# 64.net
KiCad netlist of a schematic drawn in EasyEDA Pro
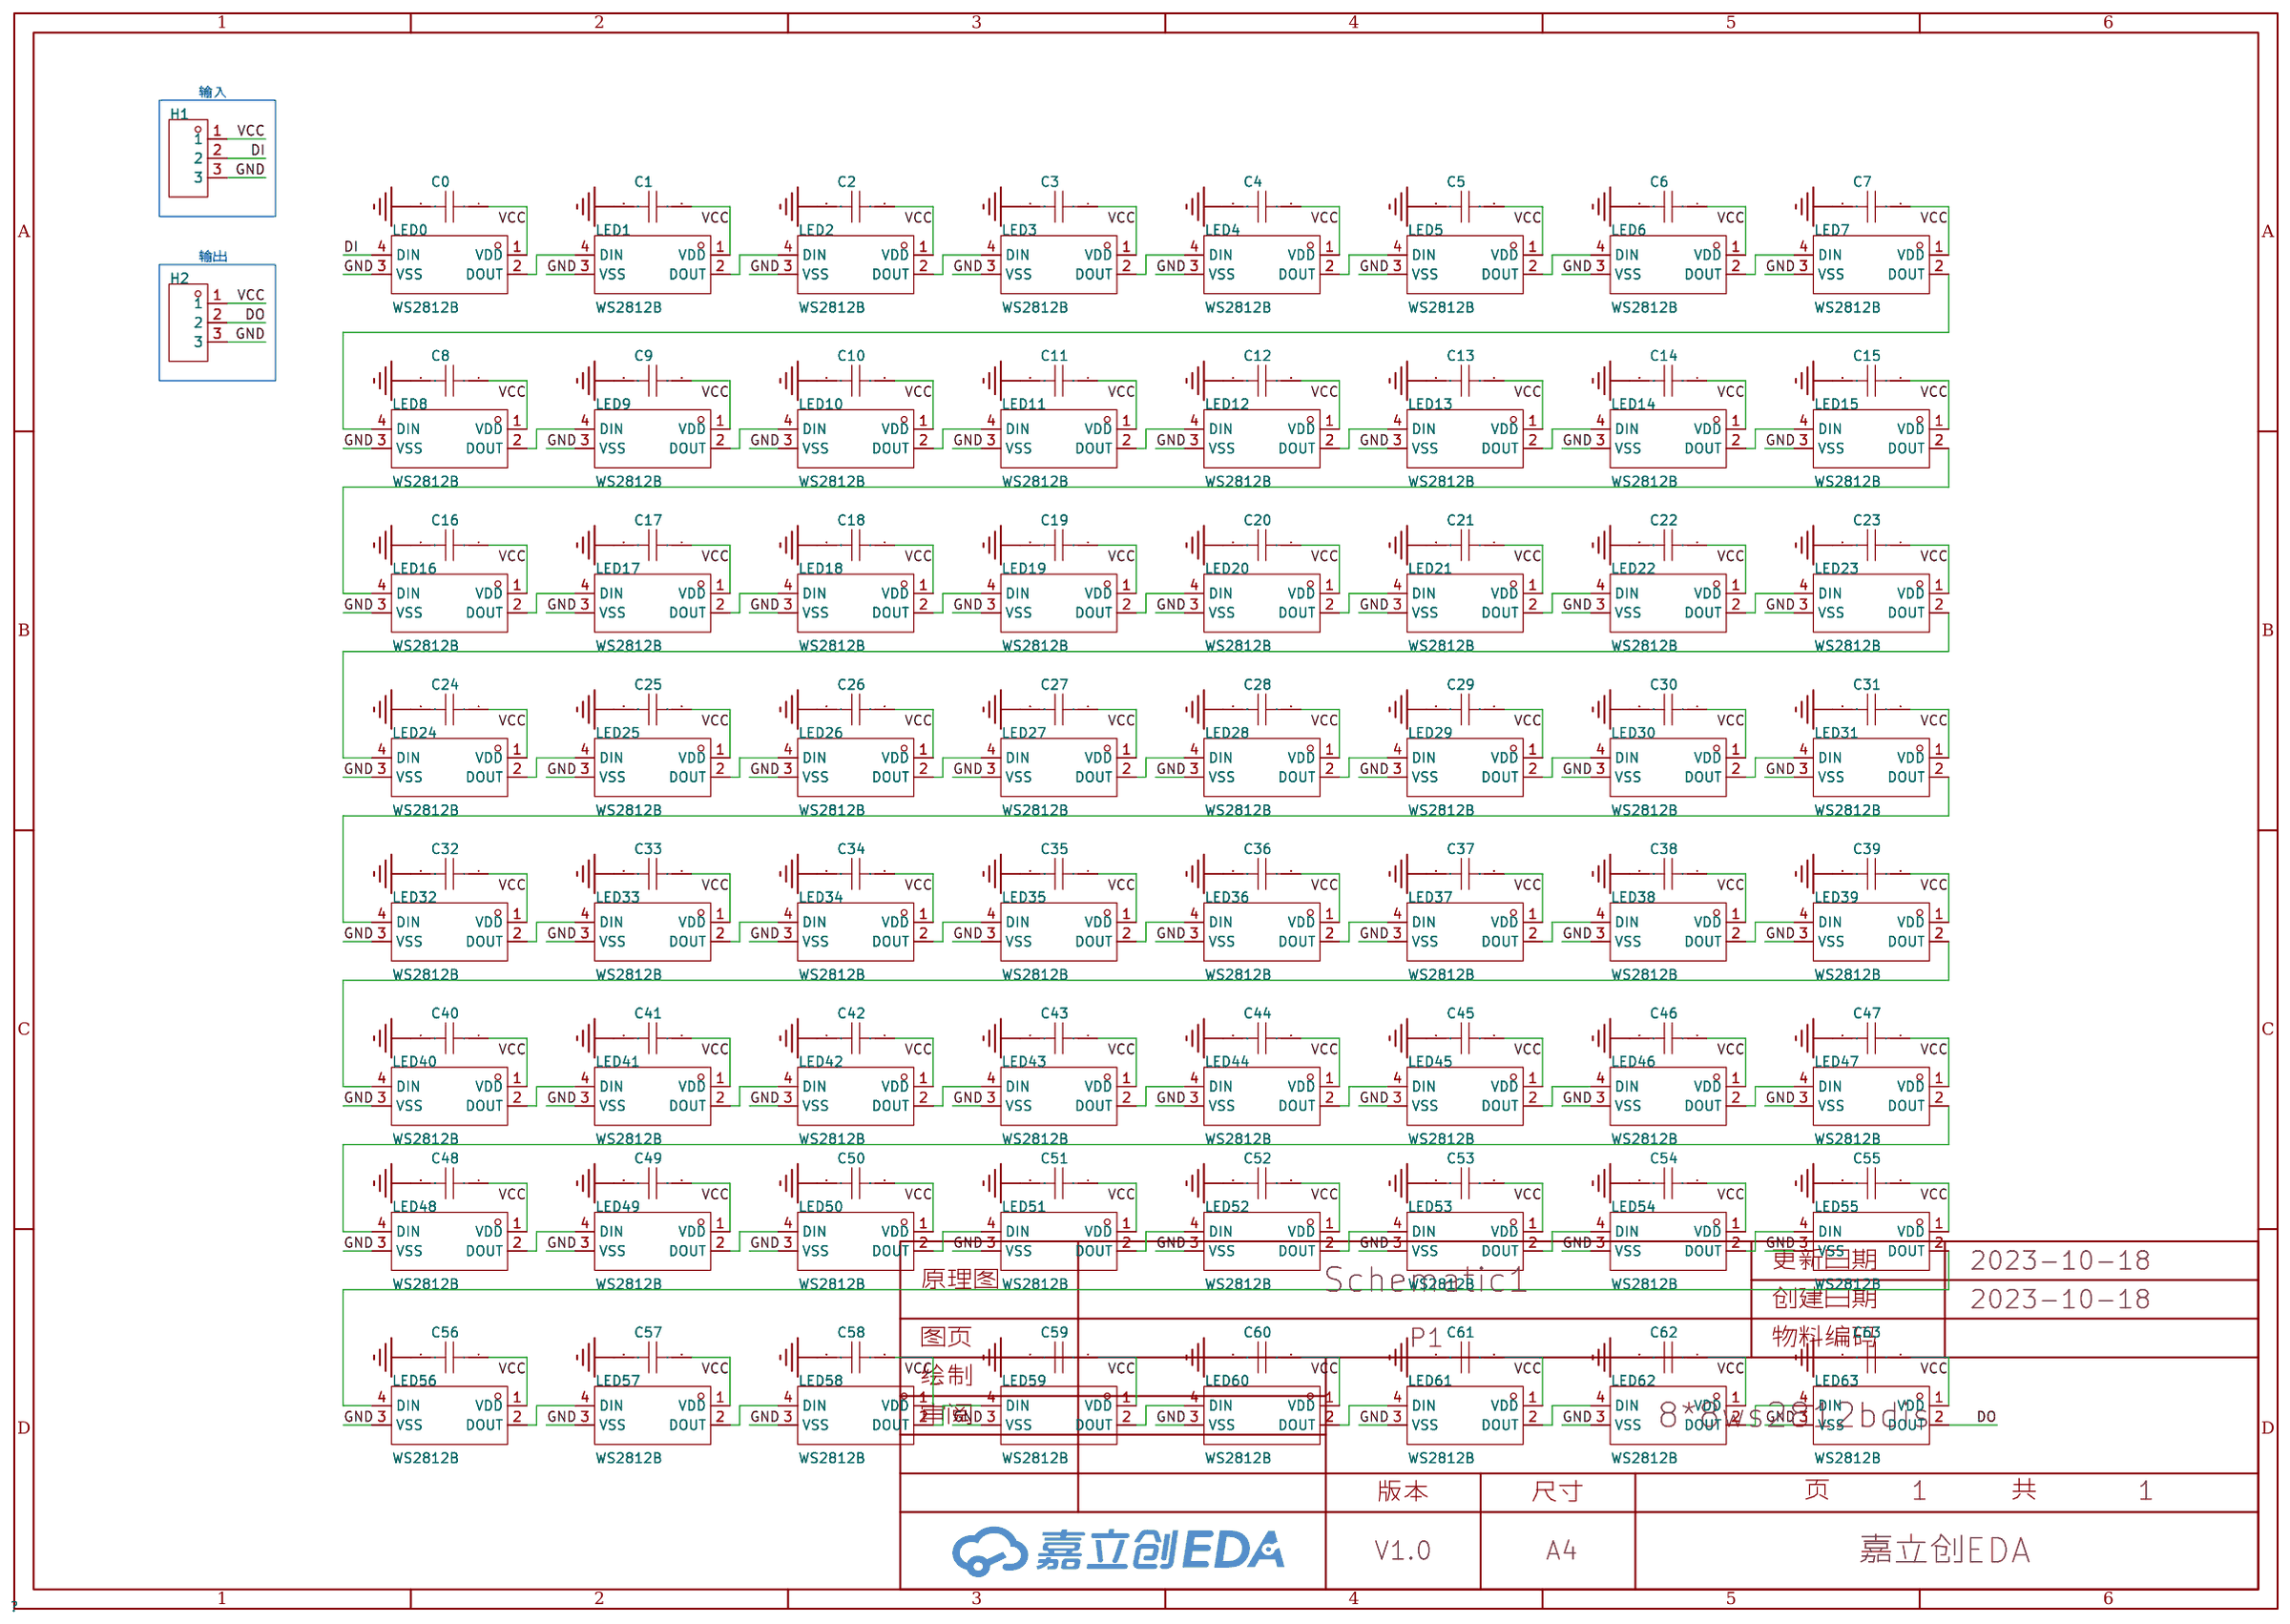
[diagram p0: schematic sheet]

(export (version "E")
  (design (tool "Eeschema 10.0.6"))
  (components
    (comp (ref "C0")
      (value "0.1uF")
      (footprint "easyedapro:C0603")
      (description "容值:0.1uF;精度:±10%;额定电压:50V;温度系数:-;")
      (fields
        (field (name "Manufacturer Part") "0603BB104K500NGT")
        (field (name "Manufacturer") "Knowles(楼氏)")
      )
      (libsource (lib "easyedapro") (part "0603BB104K500NGT"))
    )
    (comp (ref "C1")
      (value "0.1uF")
      (footprint "easyedapro:C0603")
      (description "容值:0.1uF;精度:±10%;额定电压:50V;温度系数:-;")
      (fields
        (field (name "Manufacturer Part") "0603BB104K500NGT")
        (field (name "Manufacturer") "Knowles(楼氏)")
      )
      (libsource (lib "easyedapro") (part "0603BB104K500NGT"))
    )
    (comp (ref "C2")
      (value "0.1uF")
      (footprint "easyedapro:C0603")
      (description "容值:0.1uF;精度:±10%;额定电压:50V;温度系数:-;")
      (fields
        (field (name "Manufacturer Part") "0603BB104K500NGT")
        (field (name "Manufacturer") "Knowles(楼氏)")
      )
      (libsource (lib "easyedapro") (part "0603BB104K500NGT"))
    )
    (comp (ref "C3")
      (value "0.1uF")
      (footprint "easyedapro:C0603")
      (description "容值:0.1uF;精度:±10%;额定电压:50V;温度系数:-;")
      (fields
        (field (name "Manufacturer Part") "0603BB104K500NGT")
        (field (name "Manufacturer") "Knowles(楼氏)")
      )
      (libsource (lib "easyedapro") (part "0603BB104K500NGT"))
    )
    (comp (ref "C4")
      (value "0.1uF")
      (footprint "easyedapro:C0603")
      (description "容值:0.1uF;精度:±10%;额定电压:50V;温度系数:-;")
      (fields
        (field (name "Manufacturer Part") "0603BB104K500NGT")
        (field (name "Manufacturer") "Knowles(楼氏)")
      )
      (libsource (lib "easyedapro") (part "0603BB104K500NGT"))
    )
    (comp (ref "C5")
      (value "0.1uF")
      (footprint "easyedapro:C0603")
      (description "容值:0.1uF;精度:±10%;额定电压:50V;温度系数:-;")
      (fields
        (field (name "Manufacturer Part") "0603BB104K500NGT")
        (field (name "Manufacturer") "Knowles(楼氏)")
      )
      (libsource (lib "easyedapro") (part "0603BB104K500NGT"))
    )
    (comp (ref "C6")
      (value "0.1uF")
      (footprint "easyedapro:C0603")
      (description "容值:0.1uF;精度:±10%;额定电压:50V;温度系数:-;")
      (fields
        (field (name "Manufacturer Part") "0603BB104K500NGT")
        (field (name "Manufacturer") "Knowles(楼氏)")
      )
      (libsource (lib "easyedapro") (part "0603BB104K500NGT"))
    )
    (comp (ref "C7")
      (value "0.1uF")
      (footprint "easyedapro:C0603")
      (description "容值:0.1uF;精度:±10%;额定电压:50V;温度系数:-;")
      (fields
        (field (name "Manufacturer Part") "0603BB104K500NGT")
        (field (name "Manufacturer") "Knowles(楼氏)")
      )
      (libsource (lib "easyedapro") (part "0603BB104K500NGT"))
    )
    (comp (ref "C8")
      (value "0.1uF")
      (footprint "easyedapro:C0603")
      (description "容值:0.1uF;精度:±10%;额定电压:50V;温度系数:-;")
      (fields
        (field (name "Manufacturer Part") "0603BB104K500NGT")
        (field (name "Manufacturer") "Knowles(楼氏)")
      )
      (libsource (lib "easyedapro") (part "0603BB104K500NGT"))
    )
    (comp (ref "C9")
      (value "0.1uF")
      (footprint "easyedapro:C0603")
      (description "容值:0.1uF;精度:±10%;额定电压:50V;温度系数:-;")
      (fields
        (field (name "Manufacturer Part") "0603BB104K500NGT")
        (field (name "Manufacturer") "Knowles(楼氏)")
      )
      (libsource (lib "easyedapro") (part "0603BB104K500NGT"))
    )
    (comp (ref "C10")
      (value "0.1uF")
      (footprint "easyedapro:C0603")
      (description "容值:0.1uF;精度:±10%;额定电压:50V;温度系数:-;")
      (fields
        (field (name "Manufacturer Part") "0603BB104K500NGT")
        (field (name "Manufacturer") "Knowles(楼氏)")
      )
      (libsource (lib "easyedapro") (part "0603BB104K500NGT"))
    )
    (comp (ref "C11")
      (value "0.1uF")
      (footprint "easyedapro:C0603")
      (description "容值:0.1uF;精度:±10%;额定电压:50V;温度系数:-;")
      (fields
        (field (name "Manufacturer Part") "0603BB104K500NGT")
        (field (name "Manufacturer") "Knowles(楼氏)")
      )
      (libsource (lib "easyedapro") (part "0603BB104K500NGT"))
    )
    (comp (ref "C12")
      (value "0.1uF")
      (footprint "easyedapro:C0603")
      (description "容值:0.1uF;精度:±10%;额定电压:50V;温度系数:-;")
      (fields
        (field (name "Manufacturer Part") "0603BB104K500NGT")
        (field (name "Manufacturer") "Knowles(楼氏)")
      )
      (libsource (lib "easyedapro") (part "0603BB104K500NGT"))
    )
    (comp (ref "C13")
      (value "0.1uF")
      (footprint "easyedapro:C0603")
      (description "容值:0.1uF;精度:±10%;额定电压:50V;温度系数:-;")
      (fields
        (field (name "Manufacturer Part") "0603BB104K500NGT")
        (field (name "Manufacturer") "Knowles(楼氏)")
      )
      (libsource (lib "easyedapro") (part "0603BB104K500NGT"))
    )
    (comp (ref "C14")
      (value "0.1uF")
      (footprint "easyedapro:C0603")
      (description "容值:0.1uF;精度:±10%;额定电压:50V;温度系数:-;")
      (fields
        (field (name "Manufacturer Part") "0603BB104K500NGT")
        (field (name "Manufacturer") "Knowles(楼氏)")
      )
      (libsource (lib "easyedapro") (part "0603BB104K500NGT"))
    )
    (comp (ref "C15")
      (value "0.1uF")
      (footprint "easyedapro:C0603")
      (description "容值:0.1uF;精度:±10%;额定电压:50V;温度系数:-;")
      (fields
        (field (name "Manufacturer Part") "0603BB104K500NGT")
        (field (name "Manufacturer") "Knowles(楼氏)")
      )
      (libsource (lib "easyedapro") (part "0603BB104K500NGT"))
    )
    (comp (ref "C16")
      (value "0.1uF")
      (footprint "easyedapro:C0603")
      (description "容值:0.1uF;精度:±10%;额定电压:50V;温度系数:-;")
      (fields
        (field (name "Manufacturer Part") "0603BB104K500NGT")
        (field (name "Manufacturer") "Knowles(楼氏)")
      )
      (libsource (lib "easyedapro") (part "0603BB104K500NGT"))
    )
    (comp (ref "C17")
      (value "0.1uF")
      (footprint "easyedapro:C0603")
      (description "容值:0.1uF;精度:±10%;额定电压:50V;温度系数:-;")
      (fields
        (field (name "Manufacturer Part") "0603BB104K500NGT")
        (field (name "Manufacturer") "Knowles(楼氏)")
      )
      (libsource (lib "easyedapro") (part "0603BB104K500NGT"))
    )
    (comp (ref "C18")
      (value "0.1uF")
      (footprint "easyedapro:C0603")
      (description "容值:0.1uF;精度:±10%;额定电压:50V;温度系数:-;")
      (fields
        (field (name "Manufacturer Part") "0603BB104K500NGT")
        (field (name "Manufacturer") "Knowles(楼氏)")
      )
      (libsource (lib "easyedapro") (part "0603BB104K500NGT"))
    )
    (comp (ref "C19")
      (value "0.1uF")
      (footprint "easyedapro:C0603")
      (description "容值:0.1uF;精度:±10%;额定电压:50V;温度系数:-;")
      (fields
        (field (name "Manufacturer Part") "0603BB104K500NGT")
        (field (name "Manufacturer") "Knowles(楼氏)")
      )
      (libsource (lib "easyedapro") (part "0603BB104K500NGT"))
    )
    (comp (ref "C20")
      (value "0.1uF")
      (footprint "easyedapro:C0603")
      (description "容值:0.1uF;精度:±10%;额定电压:50V;温度系数:-;")
      (fields
        (field (name "Manufacturer Part") "0603BB104K500NGT")
        (field (name "Manufacturer") "Knowles(楼氏)")
      )
      (libsource (lib "easyedapro") (part "0603BB104K500NGT"))
    )
    (comp (ref "C21")
      (value "0.1uF")
      (footprint "easyedapro:C0603")
      (description "容值:0.1uF;精度:±10%;额定电压:50V;温度系数:-;")
      (fields
        (field (name "Manufacturer Part") "0603BB104K500NGT")
        (field (name "Manufacturer") "Knowles(楼氏)")
      )
      (libsource (lib "easyedapro") (part "0603BB104K500NGT"))
    )
    (comp (ref "C22")
      (value "0.1uF")
      (footprint "easyedapro:C0603")
      (description "容值:0.1uF;精度:±10%;额定电压:50V;温度系数:-;")
      (fields
        (field (name "Manufacturer Part") "0603BB104K500NGT")
        (field (name "Manufacturer") "Knowles(楼氏)")
      )
      (libsource (lib "easyedapro") (part "0603BB104K500NGT"))
    )
    (comp (ref "C23")
      (value "0.1uF")
      (footprint "easyedapro:C0603")
      (description "容值:0.1uF;精度:±10%;额定电压:50V;温度系数:-;")
      (fields
        (field (name "Manufacturer Part") "0603BB104K500NGT")
        (field (name "Manufacturer") "Knowles(楼氏)")
      )
      (libsource (lib "easyedapro") (part "0603BB104K500NGT"))
    )
    (comp (ref "C24")
      (value "0.1uF")
      (footprint "easyedapro:C0603")
      (description "容值:0.1uF;精度:±10%;额定电压:50V;温度系数:-;")
      (fields
        (field (name "Manufacturer Part") "0603BB104K500NGT")
        (field (name "Manufacturer") "Knowles(楼氏)")
      )
      (libsource (lib "easyedapro") (part "0603BB104K500NGT"))
    )
    (comp (ref "C25")
      (value "0.1uF")
      (footprint "easyedapro:C0603")
      (description "容值:0.1uF;精度:±10%;额定电压:50V;温度系数:-;")
      (fields
        (field (name "Manufacturer Part") "0603BB104K500NGT")
        (field (name "Manufacturer") "Knowles(楼氏)")
      )
      (libsource (lib "easyedapro") (part "0603BB104K500NGT"))
    )
    (comp (ref "C26")
      (value "0.1uF")
      (footprint "easyedapro:C0603")
      (description "容值:0.1uF;精度:±10%;额定电压:50V;温度系数:-;")
      (fields
        (field (name "Manufacturer Part") "0603BB104K500NGT")
        (field (name "Manufacturer") "Knowles(楼氏)")
      )
      (libsource (lib "easyedapro") (part "0603BB104K500NGT"))
    )
    (comp (ref "C27")
      (value "0.1uF")
      (footprint "easyedapro:C0603")
      (description "容值:0.1uF;精度:±10%;额定电压:50V;温度系数:-;")
      (fields
        (field (name "Manufacturer Part") "0603BB104K500NGT")
        (field (name "Manufacturer") "Knowles(楼氏)")
      )
      (libsource (lib "easyedapro") (part "0603BB104K500NGT"))
    )
    (comp (ref "C28")
      (value "0.1uF")
      (footprint "easyedapro:C0603")
      (description "容值:0.1uF;精度:±10%;额定电压:50V;温度系数:-;")
      (fields
        (field (name "Manufacturer Part") "0603BB104K500NGT")
        (field (name "Manufacturer") "Knowles(楼氏)")
      )
      (libsource (lib "easyedapro") (part "0603BB104K500NGT"))
    )
    (comp (ref "C29")
      (value "0.1uF")
      (footprint "easyedapro:C0603")
      (description "容值:0.1uF;精度:±10%;额定电压:50V;温度系数:-;")
      (fields
        (field (name "Manufacturer Part") "0603BB104K500NGT")
        (field (name "Manufacturer") "Knowles(楼氏)")
      )
      (libsource (lib "easyedapro") (part "0603BB104K500NGT"))
    )
    (comp (ref "C30")
      (value "0.1uF")
      (footprint "easyedapro:C0603")
      (description "容值:0.1uF;精度:±10%;额定电压:50V;温度系数:-;")
      (fields
        (field (name "Manufacturer Part") "0603BB104K500NGT")
        (field (name "Manufacturer") "Knowles(楼氏)")
      )
      (libsource (lib "easyedapro") (part "0603BB104K500NGT"))
    )
    (comp (ref "C31")
      (value "0.1uF")
      (footprint "easyedapro:C0603")
      (description "容值:0.1uF;精度:±10%;额定电压:50V;温度系数:-;")
      (fields
        (field (name "Manufacturer Part") "0603BB104K500NGT")
        (field (name "Manufacturer") "Knowles(楼氏)")
      )
      (libsource (lib "easyedapro") (part "0603BB104K500NGT"))
    )
    (comp (ref "C32")
      (value "0.1uF")
      (footprint "easyedapro:C0603")
      (description "容值:0.1uF;精度:±10%;额定电压:50V;温度系数:-;")
      (fields
        (field (name "Manufacturer Part") "0603BB104K500NGT")
        (field (name "Manufacturer") "Knowles(楼氏)")
      )
      (libsource (lib "easyedapro") (part "0603BB104K500NGT"))
    )
    (comp (ref "C33")
      (value "0.1uF")
      (footprint "easyedapro:C0603")
      (description "容值:0.1uF;精度:±10%;额定电压:50V;温度系数:-;")
      (fields
        (field (name "Manufacturer Part") "0603BB104K500NGT")
        (field (name "Manufacturer") "Knowles(楼氏)")
      )
      (libsource (lib "easyedapro") (part "0603BB104K500NGT"))
    )
    (comp (ref "C34")
      (value "0.1uF")
      (footprint "easyedapro:C0603")
      (description "容值:0.1uF;精度:±10%;额定电压:50V;温度系数:-;")
      (fields
        (field (name "Manufacturer Part") "0603BB104K500NGT")
        (field (name "Manufacturer") "Knowles(楼氏)")
      )
      (libsource (lib "easyedapro") (part "0603BB104K500NGT"))
    )
    (comp (ref "C35")
      (value "0.1uF")
      (footprint "easyedapro:C0603")
      (description "容值:0.1uF;精度:±10%;额定电压:50V;温度系数:-;")
      (fields
        (field (name "Manufacturer Part") "0603BB104K500NGT")
        (field (name "Manufacturer") "Knowles(楼氏)")
      )
      (libsource (lib "easyedapro") (part "0603BB104K500NGT"))
    )
    (comp (ref "C36")
      (value "0.1uF")
      (footprint "easyedapro:C0603")
      (description "容值:0.1uF;精度:±10%;额定电压:50V;温度系数:-;")
      (fields
        (field (name "Manufacturer Part") "0603BB104K500NGT")
        (field (name "Manufacturer") "Knowles(楼氏)")
      )
      (libsource (lib "easyedapro") (part "0603BB104K500NGT"))
    )
    (comp (ref "C37")
      (value "0.1uF")
      (footprint "easyedapro:C0603")
      (description "容值:0.1uF;精度:±10%;额定电压:50V;温度系数:-;")
      (fields
        (field (name "Manufacturer Part") "0603BB104K500NGT")
        (field (name "Manufacturer") "Knowles(楼氏)")
      )
      (libsource (lib "easyedapro") (part "0603BB104K500NGT"))
    )
    (comp (ref "C38")
      (value "0.1uF")
      (footprint "easyedapro:C0603")
      (description "容值:0.1uF;精度:±10%;额定电压:50V;温度系数:-;")
      (fields
        (field (name "Manufacturer Part") "0603BB104K500NGT")
        (field (name "Manufacturer") "Knowles(楼氏)")
      )
      (libsource (lib "easyedapro") (part "0603BB104K500NGT"))
    )
    (comp (ref "C39")
      (value "0.1uF")
      (footprint "easyedapro:C0603")
      (description "容值:0.1uF;精度:±10%;额定电压:50V;温度系数:-;")
      (fields
        (field (name "Manufacturer Part") "0603BB104K500NGT")
        (field (name "Manufacturer") "Knowles(楼氏)")
      )
      (libsource (lib "easyedapro") (part "0603BB104K500NGT"))
    )
    (comp (ref "C40")
      (value "0.1uF")
      (footprint "easyedapro:C0603")
      (description "容值:0.1uF;精度:±10%;额定电压:50V;温度系数:-;")
      (fields
        (field (name "Manufacturer Part") "0603BB104K500NGT")
        (field (name "Manufacturer") "Knowles(楼氏)")
      )
      (libsource (lib "easyedapro") (part "0603BB104K500NGT"))
    )
    (comp (ref "C41")
      (value "0.1uF")
      (footprint "easyedapro:C0603")
      (description "容值:0.1uF;精度:±10%;额定电压:50V;温度系数:-;")
      (fields
        (field (name "Manufacturer Part") "0603BB104K500NGT")
        (field (name "Manufacturer") "Knowles(楼氏)")
      )
      (libsource (lib "easyedapro") (part "0603BB104K500NGT"))
    )
    (comp (ref "C42")
      (value "0.1uF")
      (footprint "easyedapro:C0603")
      (description "容值:0.1uF;精度:±10%;额定电压:50V;温度系数:-;")
      (fields
        (field (name "Manufacturer Part") "0603BB104K500NGT")
        (field (name "Manufacturer") "Knowles(楼氏)")
      )
      (libsource (lib "easyedapro") (part "0603BB104K500NGT"))
    )
    (comp (ref "C43")
      (value "0.1uF")
      (footprint "easyedapro:C0603")
      (description "容值:0.1uF;精度:±10%;额定电压:50V;温度系数:-;")
      (fields
        (field (name "Manufacturer Part") "0603BB104K500NGT")
        (field (name "Manufacturer") "Knowles(楼氏)")
      )
      (libsource (lib "easyedapro") (part "0603BB104K500NGT"))
    )
    (comp (ref "C44")
      (value "0.1uF")
      (footprint "easyedapro:C0603")
      (description "容值:0.1uF;精度:±10%;额定电压:50V;温度系数:-;")
      (fields
        (field (name "Manufacturer Part") "0603BB104K500NGT")
        (field (name "Manufacturer") "Knowles(楼氏)")
      )
      (libsource (lib "easyedapro") (part "0603BB104K500NGT"))
    )
    (comp (ref "C45")
      (value "0.1uF")
      (footprint "easyedapro:C0603")
      (description "容值:0.1uF;精度:±10%;额定电压:50V;温度系数:-;")
      (fields
        (field (name "Manufacturer Part") "0603BB104K500NGT")
        (field (name "Manufacturer") "Knowles(楼氏)")
      )
      (libsource (lib "easyedapro") (part "0603BB104K500NGT"))
    )
    (comp (ref "C46")
      (value "0.1uF")
      (footprint "easyedapro:C0603")
      (description "容值:0.1uF;精度:±10%;额定电压:50V;温度系数:-;")
      (fields
        (field (name "Manufacturer Part") "0603BB104K500NGT")
        (field (name "Manufacturer") "Knowles(楼氏)")
      )
      (libsource (lib "easyedapro") (part "0603BB104K500NGT"))
    )
    (comp (ref "C47")
      (value "0.1uF")
      (footprint "easyedapro:C0603")
      (description "容值:0.1uF;精度:±10%;额定电压:50V;温度系数:-;")
      (fields
        (field (name "Manufacturer Part") "0603BB104K500NGT")
        (field (name "Manufacturer") "Knowles(楼氏)")
      )
      (libsource (lib "easyedapro") (part "0603BB104K500NGT"))
    )
    (comp (ref "C48")
      (value "0.1uF")
      (footprint "easyedapro:C0603")
      (description "容值:0.1uF;精度:±10%;额定电压:50V;温度系数:-;")
      (fields
        (field (name "Manufacturer Part") "0603BB104K500NGT")
        (field (name "Manufacturer") "Knowles(楼氏)")
      )
      (libsource (lib "easyedapro") (part "0603BB104K500NGT"))
    )
    (comp (ref "C49")
      (value "0.1uF")
      (footprint "easyedapro:C0603")
      (description "容值:0.1uF;精度:±10%;额定电压:50V;温度系数:-;")
      (fields
        (field (name "Manufacturer Part") "0603BB104K500NGT")
        (field (name "Manufacturer") "Knowles(楼氏)")
      )
      (libsource (lib "easyedapro") (part "0603BB104K500NGT"))
    )
    (comp (ref "C50")
      (value "0.1uF")
      (footprint "easyedapro:C0603")
      (description "容值:0.1uF;精度:±10%;额定电压:50V;温度系数:-;")
      (fields
        (field (name "Manufacturer Part") "0603BB104K500NGT")
        (field (name "Manufacturer") "Knowles(楼氏)")
      )
      (libsource (lib "easyedapro") (part "0603BB104K500NGT"))
    )
    (comp (ref "C51")
      (value "0.1uF")
      (footprint "easyedapro:C0603")
      (description "容值:0.1uF;精度:±10%;额定电压:50V;温度系数:-;")
      (fields
        (field (name "Manufacturer Part") "0603BB104K500NGT")
        (field (name "Manufacturer") "Knowles(楼氏)")
      )
      (libsource (lib "easyedapro") (part "0603BB104K500NGT"))
    )
    (comp (ref "C52")
      (value "0.1uF")
      (footprint "easyedapro:C0603")
      (description "容值:0.1uF;精度:±10%;额定电压:50V;温度系数:-;")
      (fields
        (field (name "Manufacturer Part") "0603BB104K500NGT")
        (field (name "Manufacturer") "Knowles(楼氏)")
      )
      (libsource (lib "easyedapro") (part "0603BB104K500NGT"))
    )
    (comp (ref "C53")
      (value "0.1uF")
      (footprint "easyedapro:C0603")
      (description "容值:0.1uF;精度:±10%;额定电压:50V;温度系数:-;")
      (fields
        (field (name "Manufacturer Part") "0603BB104K500NGT")
        (field (name "Manufacturer") "Knowles(楼氏)")
      )
      (libsource (lib "easyedapro") (part "0603BB104K500NGT"))
    )
    (comp (ref "C54")
      (value "0.1uF")
      (footprint "easyedapro:C0603")
      (description "容值:0.1uF;精度:±10%;额定电压:50V;温度系数:-;")
      (fields
        (field (name "Manufacturer Part") "0603BB104K500NGT")
        (field (name "Manufacturer") "Knowles(楼氏)")
      )
      (libsource (lib "easyedapro") (part "0603BB104K500NGT"))
    )
    (comp (ref "C55")
      (value "0.1uF")
      (footprint "easyedapro:C0603")
      (description "容值:0.1uF;精度:±10%;额定电压:50V;温度系数:-;")
      (fields
        (field (name "Manufacturer Part") "0603BB104K500NGT")
        (field (name "Manufacturer") "Knowles(楼氏)")
      )
      (libsource (lib "easyedapro") (part "0603BB104K500NGT"))
    )
    (comp (ref "C56")
      (value "0.1uF")
      (footprint "easyedapro:C0603")
      (description "容值:0.1uF;精度:±10%;额定电压:50V;温度系数:-;")
      (fields
        (field (name "Manufacturer Part") "0603BB104K500NGT")
        (field (name "Manufacturer") "Knowles(楼氏)")
      )
      (libsource (lib "easyedapro") (part "0603BB104K500NGT"))
    )
    (comp (ref "C57")
      (value "0.1uF")
      (footprint "easyedapro:C0603")
      (description "容值:0.1uF;精度:±10%;额定电压:50V;温度系数:-;")
      (fields
        (field (name "Manufacturer Part") "0603BB104K500NGT")
        (field (name "Manufacturer") "Knowles(楼氏)")
      )
      (libsource (lib "easyedapro") (part "0603BB104K500NGT"))
    )
    (comp (ref "C58")
      (value "0.1uF")
      (footprint "easyedapro:C0603")
      (description "容值:0.1uF;精度:±10%;额定电压:50V;温度系数:-;")
      (fields
        (field (name "Manufacturer Part") "0603BB104K500NGT")
        (field (name "Manufacturer") "Knowles(楼氏)")
      )
      (libsource (lib "easyedapro") (part "0603BB104K500NGT"))
    )
    (comp (ref "C59")
      (value "0.1uF")
      (footprint "easyedapro:C0603")
      (description "容值:0.1uF;精度:±10%;额定电压:50V;温度系数:-;")
      (fields
        (field (name "Manufacturer Part") "0603BB104K500NGT")
        (field (name "Manufacturer") "Knowles(楼氏)")
      )
      (libsource (lib "easyedapro") (part "0603BB104K500NGT"))
    )
    (comp (ref "C60")
      (value "0.1uF")
      (footprint "easyedapro:C0603")
      (description "容值:0.1uF;精度:±10%;额定电压:50V;温度系数:-;")
      (fields
        (field (name "Manufacturer Part") "0603BB104K500NGT")
        (field (name "Manufacturer") "Knowles(楼氏)")
      )
      (libsource (lib "easyedapro") (part "0603BB104K500NGT"))
    )
    (comp (ref "C61")
      (value "0.1uF")
      (footprint "easyedapro:C0603")
      (description "容值:0.1uF;精度:±10%;额定电压:50V;温度系数:-;")
      (fields
        (field (name "Manufacturer Part") "0603BB104K500NGT")
        (field (name "Manufacturer") "Knowles(楼氏)")
      )
      (libsource (lib "easyedapro") (part "0603BB104K500NGT"))
    )
    (comp (ref "C62")
      (value "0.1uF")
      (footprint "easyedapro:C0603")
      (description "容值:0.1uF;精度:±10%;额定电压:50V;温度系数:-;")
      (fields
        (field (name "Manufacturer Part") "0603BB104K500NGT")
        (field (name "Manufacturer") "Knowles(楼氏)")
      )
      (libsource (lib "easyedapro") (part "0603BB104K500NGT"))
    )
    (comp (ref "C63")
      (value "0.1uF")
      (footprint "easyedapro:C0603")
      (description "容值:0.1uF;精度:±10%;额定电压:50V;温度系数:-;")
      (fields
        (field (name "Manufacturer Part") "0603BB104K500NGT")
        (field (name "Manufacturer") "Knowles(楼氏)")
      )
      (libsource (lib "easyedapro") (part "0603BB104K500NGT"))
    )
    (comp (ref "H1")
      (value "~")
      (footprint "easyedapro:HDR-TH_3P-P2.54-V-M")
      (libsource (lib "easyedapro") (part "PZ254V-11-03P_C2937625"))
    )
    (comp (ref "H2")
      (value "~")
      (footprint "easyedapro:HDR-TH_3P-P2.54-V-M")
      (libsource (lib "easyedapro") (part "PZ254V-11-03P_C2937625"))
    )
    (comp (ref "LED0")
      (value "WS2812B")
      (footprint "easyedapro:LED-SMD_4P-L5.0-W5.0-TL")
      (libsource (lib "easyedapro") (part "WS2812B_C9900004137"))
    )
    (comp (ref "LED1")
      (value "WS2812B")
      (footprint "easyedapro:LED-SMD_4P-L5.0-W5.0-TL")
      (libsource (lib "easyedapro") (part "WS2812B_C9900004137"))
    )
    (comp (ref "LED2")
      (value "WS2812B")
      (footprint "easyedapro:LED-SMD_4P-L5.0-W5.0-TL")
      (libsource (lib "easyedapro") (part "WS2812B_C9900004137"))
    )
    (comp (ref "LED3")
      (value "WS2812B")
      (footprint "easyedapro:LED-SMD_4P-L5.0-W5.0-TL")
      (libsource (lib "easyedapro") (part "WS2812B_C9900004137"))
    )
    (comp (ref "LED4")
      (value "WS2812B")
      (footprint "easyedapro:LED-SMD_4P-L5.0-W5.0-TL")
      (libsource (lib "easyedapro") (part "WS2812B_C9900004137"))
    )
    (comp (ref "LED5")
      (value "WS2812B")
      (footprint "easyedapro:LED-SMD_4P-L5.0-W5.0-TL")
      (libsource (lib "easyedapro") (part "WS2812B_C9900004137"))
    )
    (comp (ref "LED6")
      (value "WS2812B")
      (footprint "easyedapro:LED-SMD_4P-L5.0-W5.0-TL")
      (libsource (lib "easyedapro") (part "WS2812B_C9900004137"))
    )
    (comp (ref "LED7")
      (value "WS2812B")
      (footprint "easyedapro:LED-SMD_4P-L5.0-W5.0-TL")
      (libsource (lib "easyedapro") (part "WS2812B_C9900004137"))
    )
    (comp (ref "LED8")
      (value "WS2812B")
      (footprint "easyedapro:LED-SMD_4P-L5.0-W5.0-TL")
      (libsource (lib "easyedapro") (part "WS2812B_C9900004137"))
    )
    (comp (ref "LED9")
      (value "WS2812B")
      (footprint "easyedapro:LED-SMD_4P-L5.0-W5.0-TL")
      (libsource (lib "easyedapro") (part "WS2812B_C9900004137"))
    )
    (comp (ref "LED10")
      (value "WS2812B")
      (footprint "easyedapro:LED-SMD_4P-L5.0-W5.0-TL")
      (libsource (lib "easyedapro") (part "WS2812B_C9900004137"))
    )
    (comp (ref "LED11")
      (value "WS2812B")
      (footprint "easyedapro:LED-SMD_4P-L5.0-W5.0-TL")
      (libsource (lib "easyedapro") (part "WS2812B_C9900004137"))
    )
    (comp (ref "LED12")
      (value "WS2812B")
      (footprint "easyedapro:LED-SMD_4P-L5.0-W5.0-TL")
      (libsource (lib "easyedapro") (part "WS2812B_C9900004137"))
    )
    (comp (ref "LED13")
      (value "WS2812B")
      (footprint "easyedapro:LED-SMD_4P-L5.0-W5.0-TL")
      (libsource (lib "easyedapro") (part "WS2812B_C9900004137"))
    )
    (comp (ref "LED14")
      (value "WS2812B")
      (footprint "easyedapro:LED-SMD_4P-L5.0-W5.0-TL")
      (libsource (lib "easyedapro") (part "WS2812B_C9900004137"))
    )
    (comp (ref "LED15")
      (value "WS2812B")
      (footprint "easyedapro:LED-SMD_4P-L5.0-W5.0-TL")
      (libsource (lib "easyedapro") (part "WS2812B_C9900004137"))
    )
    (comp (ref "LED16")
      (value "WS2812B")
      (footprint "easyedapro:LED-SMD_4P-L5.0-W5.0-TL")
      (libsource (lib "easyedapro") (part "WS2812B_C9900004137"))
    )
    (comp (ref "LED17")
      (value "WS2812B")
      (footprint "easyedapro:LED-SMD_4P-L5.0-W5.0-TL")
      (libsource (lib "easyedapro") (part "WS2812B_C9900004137"))
    )
    (comp (ref "LED18")
      (value "WS2812B")
      (footprint "easyedapro:LED-SMD_4P-L5.0-W5.0-TL")
      (libsource (lib "easyedapro") (part "WS2812B_C9900004137"))
    )
    (comp (ref "LED19")
      (value "WS2812B")
      (footprint "easyedapro:LED-SMD_4P-L5.0-W5.0-TL")
      (libsource (lib "easyedapro") (part "WS2812B_C9900004137"))
    )
    (comp (ref "LED20")
      (value "WS2812B")
      (footprint "easyedapro:LED-SMD_4P-L5.0-W5.0-TL")
      (libsource (lib "easyedapro") (part "WS2812B_C9900004137"))
    )
    (comp (ref "LED21")
      (value "WS2812B")
      (footprint "easyedapro:LED-SMD_4P-L5.0-W5.0-TL")
      (libsource (lib "easyedapro") (part "WS2812B_C9900004137"))
    )
    (comp (ref "LED22")
      (value "WS2812B")
      (footprint "easyedapro:LED-SMD_4P-L5.0-W5.0-TL")
      (libsource (lib "easyedapro") (part "WS2812B_C9900004137"))
    )
    (comp (ref "LED23")
      (value "WS2812B")
      (footprint "easyedapro:LED-SMD_4P-L5.0-W5.0-TL")
      (libsource (lib "easyedapro") (part "WS2812B_C9900004137"))
    )
    (comp (ref "LED24")
      (value "WS2812B")
      (footprint "easyedapro:LED-SMD_4P-L5.0-W5.0-TL")
      (libsource (lib "easyedapro") (part "WS2812B_C9900004137"))
    )
    (comp (ref "LED25")
      (value "WS2812B")
      (footprint "easyedapro:LED-SMD_4P-L5.0-W5.0-TL")
      (libsource (lib "easyedapro") (part "WS2812B_C9900004137"))
    )
    (comp (ref "LED26")
      (value "WS2812B")
      (footprint "easyedapro:LED-SMD_4P-L5.0-W5.0-TL")
      (libsource (lib "easyedapro") (part "WS2812B_C9900004137"))
    )
    (comp (ref "LED27")
      (value "WS2812B")
      (footprint "easyedapro:LED-SMD_4P-L5.0-W5.0-TL")
      (libsource (lib "easyedapro") (part "WS2812B_C9900004137"))
    )
    (comp (ref "LED28")
      (value "WS2812B")
      (footprint "easyedapro:LED-SMD_4P-L5.0-W5.0-TL")
      (libsource (lib "easyedapro") (part "WS2812B_C9900004137"))
    )
    (comp (ref "LED29")
      (value "WS2812B")
      (footprint "easyedapro:LED-SMD_4P-L5.0-W5.0-TL")
      (libsource (lib "easyedapro") (part "WS2812B_C9900004137"))
    )
    (comp (ref "LED30")
      (value "WS2812B")
      (footprint "easyedapro:LED-SMD_4P-L5.0-W5.0-TL")
      (libsource (lib "easyedapro") (part "WS2812B_C9900004137"))
    )
    (comp (ref "LED31")
      (value "WS2812B")
      (footprint "easyedapro:LED-SMD_4P-L5.0-W5.0-TL")
      (libsource (lib "easyedapro") (part "WS2812B_C9900004137"))
    )
    (comp (ref "LED32")
      (value "WS2812B")
      (footprint "easyedapro:LED-SMD_4P-L5.0-W5.0-TL")
      (libsource (lib "easyedapro") (part "WS2812B_C9900004137"))
    )
    (comp (ref "LED33")
      (value "WS2812B")
      (footprint "easyedapro:LED-SMD_4P-L5.0-W5.0-TL")
      (libsource (lib "easyedapro") (part "WS2812B_C9900004137"))
    )
    (comp (ref "LED34")
      (value "WS2812B")
      (footprint "easyedapro:LED-SMD_4P-L5.0-W5.0-TL")
      (libsource (lib "easyedapro") (part "WS2812B_C9900004137"))
    )
    (comp (ref "LED35")
      (value "WS2812B")
      (footprint "easyedapro:LED-SMD_4P-L5.0-W5.0-TL")
      (libsource (lib "easyedapro") (part "WS2812B_C9900004137"))
    )
    (comp (ref "LED36")
      (value "WS2812B")
      (footprint "easyedapro:LED-SMD_4P-L5.0-W5.0-TL")
      (libsource (lib "easyedapro") (part "WS2812B_C9900004137"))
    )
    (comp (ref "LED37")
      (value "WS2812B")
      (footprint "easyedapro:LED-SMD_4P-L5.0-W5.0-TL")
      (libsource (lib "easyedapro") (part "WS2812B_C9900004137"))
    )
    (comp (ref "LED38")
      (value "WS2812B")
      (footprint "easyedapro:LED-SMD_4P-L5.0-W5.0-TL")
      (libsource (lib "easyedapro") (part "WS2812B_C9900004137"))
    )
    (comp (ref "LED39")
      (value "WS2812B")
      (footprint "easyedapro:LED-SMD_4P-L5.0-W5.0-TL")
      (libsource (lib "easyedapro") (part "WS2812B_C9900004137"))
    )
    (comp (ref "LED40")
      (value "WS2812B")
      (footprint "easyedapro:LED-SMD_4P-L5.0-W5.0-TL")
      (libsource (lib "easyedapro") (part "WS2812B_C9900004137"))
    )
    (comp (ref "LED41")
      (value "WS2812B")
      (footprint "easyedapro:LED-SMD_4P-L5.0-W5.0-TL")
      (libsource (lib "easyedapro") (part "WS2812B_C9900004137"))
    )
    (comp (ref "LED42")
      (value "WS2812B")
      (footprint "easyedapro:LED-SMD_4P-L5.0-W5.0-TL")
      (libsource (lib "easyedapro") (part "WS2812B_C9900004137"))
    )
    (comp (ref "LED43")
      (value "WS2812B")
      (footprint "easyedapro:LED-SMD_4P-L5.0-W5.0-TL")
      (libsource (lib "easyedapro") (part "WS2812B_C9900004137"))
    )
    (comp (ref "LED44")
      (value "WS2812B")
      (footprint "easyedapro:LED-SMD_4P-L5.0-W5.0-TL")
      (libsource (lib "easyedapro") (part "WS2812B_C9900004137"))
    )
    (comp (ref "LED45")
      (value "WS2812B")
      (footprint "easyedapro:LED-SMD_4P-L5.0-W5.0-TL")
      (libsource (lib "easyedapro") (part "WS2812B_C9900004137"))
    )
    (comp (ref "LED46")
      (value "WS2812B")
      (footprint "easyedapro:LED-SMD_4P-L5.0-W5.0-TL")
      (libsource (lib "easyedapro") (part "WS2812B_C9900004137"))
    )
    (comp (ref "LED47")
      (value "WS2812B")
      (footprint "easyedapro:LED-SMD_4P-L5.0-W5.0-TL")
      (libsource (lib "easyedapro") (part "WS2812B_C9900004137"))
    )
    (comp (ref "LED48")
      (value "WS2812B")
      (footprint "easyedapro:LED-SMD_4P-L5.0-W5.0-TL")
      (libsource (lib "easyedapro") (part "WS2812B_C9900004137"))
    )
    (comp (ref "LED49")
      (value "WS2812B")
      (footprint "easyedapro:LED-SMD_4P-L5.0-W5.0-TL")
      (libsource (lib "easyedapro") (part "WS2812B_C9900004137"))
    )
    (comp (ref "LED50")
      (value "WS2812B")
      (footprint "easyedapro:LED-SMD_4P-L5.0-W5.0-TL")
      (libsource (lib "easyedapro") (part "WS2812B_C9900004137"))
    )
    (comp (ref "LED51")
      (value "WS2812B")
      (footprint "easyedapro:LED-SMD_4P-L5.0-W5.0-TL")
      (libsource (lib "easyedapro") (part "WS2812B_C9900004137"))
    )
    (comp (ref "LED52")
      (value "WS2812B")
      (footprint "easyedapro:LED-SMD_4P-L5.0-W5.0-TL")
      (libsource (lib "easyedapro") (part "WS2812B_C9900004137"))
    )
    (comp (ref "LED53")
      (value "WS2812B")
      (footprint "easyedapro:LED-SMD_4P-L5.0-W5.0-TL")
      (libsource (lib "easyedapro") (part "WS2812B_C9900004137"))
    )
    (comp (ref "LED54")
      (value "WS2812B")
      (footprint "easyedapro:LED-SMD_4P-L5.0-W5.0-TL")
      (libsource (lib "easyedapro") (part "WS2812B_C9900004137"))
    )
    (comp (ref "LED55")
      (value "WS2812B")
      (footprint "easyedapro:LED-SMD_4P-L5.0-W5.0-TL")
      (libsource (lib "easyedapro") (part "WS2812B_C9900004137"))
    )
    (comp (ref "LED56")
      (value "WS2812B")
      (footprint "easyedapro:LED-SMD_4P-L5.0-W5.0-TL")
      (libsource (lib "easyedapro") (part "WS2812B_C9900004137"))
    )
    (comp (ref "LED57")
      (value "WS2812B")
      (footprint "easyedapro:LED-SMD_4P-L5.0-W5.0-TL")
      (libsource (lib "easyedapro") (part "WS2812B_C9900004137"))
    )
    (comp (ref "LED58")
      (value "WS2812B")
      (footprint "easyedapro:LED-SMD_4P-L5.0-W5.0-TL")
      (libsource (lib "easyedapro") (part "WS2812B_C9900004137"))
    )
    (comp (ref "LED59")
      (value "WS2812B")
      (footprint "easyedapro:LED-SMD_4P-L5.0-W5.0-TL")
      (libsource (lib "easyedapro") (part "WS2812B_C9900004137"))
    )
    (comp (ref "LED60")
      (value "WS2812B")
      (footprint "easyedapro:LED-SMD_4P-L5.0-W5.0-TL")
      (libsource (lib "easyedapro") (part "WS2812B_C9900004137"))
    )
    (comp (ref "LED61")
      (value "WS2812B")
      (footprint "easyedapro:LED-SMD_4P-L5.0-W5.0-TL")
      (libsource (lib "easyedapro") (part "WS2812B_C9900004137"))
    )
    (comp (ref "LED62")
      (value "WS2812B")
      (footprint "easyedapro:LED-SMD_4P-L5.0-W5.0-TL")
      (libsource (lib "easyedapro") (part "WS2812B_C9900004137"))
    )
    (comp (ref "LED63")
      (value "WS2812B")
      (footprint "easyedapro:LED-SMD_4P-L5.0-W5.0-TL")
      (libsource (lib "easyedapro") (part "WS2812B_C9900004137"))
    )
  )
  (nets
    (net (code "1") (name "/DI") (class "Default")
      (node (ref "H1") (pin "2") (pinfunction "2_2") (pintype "input"))
      (node (ref "LED0") (pin "4") (pinfunction "DIN_4") (pintype "input"))
    )
    (net (code "2") (name "/DO") (class "Default")
      (node (ref "H2") (pin "2") (pinfunction "2_2") (pintype "input"))
      (node (ref "LED63") (pin "2") (pinfunction "DOUT_2") (pintype "input"))
    )
    (net (code "3") (name "/VCC") (class "Default")
      (node (ref "C0") (pin "1") (pinfunction "1_1") (pintype "input"))
      (node (ref "C1") (pin "1") (pinfunction "1_1") (pintype "input"))
      (node (ref "C10") (pin "1") (pinfunction "1_1") (pintype "input"))
      (node (ref "C11") (pin "1") (pinfunction "1_1") (pintype "input"))
      (node (ref "C12") (pin "1") (pinfunction "1_1") (pintype "input"))
      (node (ref "C13") (pin "1") (pinfunction "1_1") (pintype "input"))
      (node (ref "C14") (pin "1") (pinfunction "1_1") (pintype "input"))
      (node (ref "C15") (pin "1") (pinfunction "1_1") (pintype "input"))
      (node (ref "C16") (pin "1") (pinfunction "1_1") (pintype "input"))
      (node (ref "C17") (pin "1") (pinfunction "1_1") (pintype "input"))
      (node (ref "C18") (pin "1") (pinfunction "1_1") (pintype "input"))
      (node (ref "C19") (pin "1") (pinfunction "1_1") (pintype "input"))
      (node (ref "C2") (pin "1") (pinfunction "1_1") (pintype "input"))
      (node (ref "C20") (pin "1") (pinfunction "1_1") (pintype "input"))
      (node (ref "C21") (pin "1") (pinfunction "1_1") (pintype "input"))
      (node (ref "C22") (pin "1") (pinfunction "1_1") (pintype "input"))
      (node (ref "C23") (pin "1") (pinfunction "1_1") (pintype "input"))
      (node (ref "C24") (pin "1") (pinfunction "1_1") (pintype "input"))
      (node (ref "C25") (pin "1") (pinfunction "1_1") (pintype "input"))
      (node (ref "C26") (pin "1") (pinfunction "1_1") (pintype "input"))
      (node (ref "C27") (pin "1") (pinfunction "1_1") (pintype "input"))
      (node (ref "C28") (pin "1") (pinfunction "1_1") (pintype "input"))
      (node (ref "C29") (pin "1") (pinfunction "1_1") (pintype "input"))
      (node (ref "C3") (pin "1") (pinfunction "1_1") (pintype "input"))
      (node (ref "C30") (pin "1") (pinfunction "1_1") (pintype "input"))
      (node (ref "C31") (pin "1") (pinfunction "1_1") (pintype "input"))
      (node (ref "C32") (pin "1") (pinfunction "1_1") (pintype "input"))
      (node (ref "C33") (pin "1") (pinfunction "1_1") (pintype "input"))
      (node (ref "C34") (pin "1") (pinfunction "1_1") (pintype "input"))
      (node (ref "C35") (pin "1") (pinfunction "1_1") (pintype "input"))
      (node (ref "C36") (pin "1") (pinfunction "1_1") (pintype "input"))
      (node (ref "C37") (pin "1") (pinfunction "1_1") (pintype "input"))
      (node (ref "C38") (pin "1") (pinfunction "1_1") (pintype "input"))
      (node (ref "C39") (pin "1") (pinfunction "1_1") (pintype "input"))
      (node (ref "C4") (pin "1") (pinfunction "1_1") (pintype "input"))
      (node (ref "C40") (pin "1") (pinfunction "1_1") (pintype "input"))
      (node (ref "C41") (pin "1") (pinfunction "1_1") (pintype "input"))
      (node (ref "C42") (pin "1") (pinfunction "1_1") (pintype "input"))
      (node (ref "C43") (pin "1") (pinfunction "1_1") (pintype "input"))
      (node (ref "C44") (pin "1") (pinfunction "1_1") (pintype "input"))
      (node (ref "C45") (pin "1") (pinfunction "1_1") (pintype "input"))
      (node (ref "C46") (pin "1") (pinfunction "1_1") (pintype "input"))
      (node (ref "C47") (pin "1") (pinfunction "1_1") (pintype "input"))
      (node (ref "C48") (pin "1") (pinfunction "1_1") (pintype "input"))
      (node (ref "C49") (pin "1") (pinfunction "1_1") (pintype "input"))
      (node (ref "C5") (pin "1") (pinfunction "1_1") (pintype "input"))
      (node (ref "C50") (pin "1") (pinfunction "1_1") (pintype "input"))
      (node (ref "C51") (pin "1") (pinfunction "1_1") (pintype "input"))
      (node (ref "C52") (pin "1") (pinfunction "1_1") (pintype "input"))
      (node (ref "C53") (pin "1") (pinfunction "1_1") (pintype "input"))
      (node (ref "C54") (pin "1") (pinfunction "1_1") (pintype "input"))
      (node (ref "C55") (pin "1") (pinfunction "1_1") (pintype "input"))
      (node (ref "C56") (pin "1") (pinfunction "1_1") (pintype "input"))
      (node (ref "C57") (pin "1") (pinfunction "1_1") (pintype "input"))
      (node (ref "C58") (pin "1") (pinfunction "1_1") (pintype "input"))
      (node (ref "C59") (pin "1") (pinfunction "1_1") (pintype "input"))
      (node (ref "C6") (pin "1") (pinfunction "1_1") (pintype "input"))
      (node (ref "C60") (pin "1") (pinfunction "1_1") (pintype "input"))
      (node (ref "C61") (pin "1") (pinfunction "1_1") (pintype "input"))
      (node (ref "C62") (pin "1") (pinfunction "1_1") (pintype "input"))
      (node (ref "C63") (pin "1") (pinfunction "1_1") (pintype "input"))
      (node (ref "C7") (pin "1") (pinfunction "1_1") (pintype "input"))
      (node (ref "C8") (pin "1") (pinfunction "1_1") (pintype "input"))
      (node (ref "C9") (pin "1") (pinfunction "1_1") (pintype "input"))
      (node (ref "H1") (pin "1") (pinfunction "1_1") (pintype "input"))
      (node (ref "H2") (pin "1") (pinfunction "1_1") (pintype "input"))
      (node (ref "LED0") (pin "1") (pinfunction "VDD_1") (pintype "input"))
      (node (ref "LED1") (pin "1") (pinfunction "VDD_1") (pintype "input"))
      (node (ref "LED10") (pin "1") (pinfunction "VDD_1") (pintype "input"))
      (node (ref "LED11") (pin "1") (pinfunction "VDD_1") (pintype "input"))
      (node (ref "LED12") (pin "1") (pinfunction "VDD_1") (pintype "input"))
      (node (ref "LED13") (pin "1") (pinfunction "VDD_1") (pintype "input"))
      (node (ref "LED14") (pin "1") (pinfunction "VDD_1") (pintype "input"))
      (node (ref "LED15") (pin "1") (pinfunction "VDD_1") (pintype "input"))
      (node (ref "LED16") (pin "1") (pinfunction "VDD_1") (pintype "input"))
      (node (ref "LED17") (pin "1") (pinfunction "VDD_1") (pintype "input"))
      (node (ref "LED18") (pin "1") (pinfunction "VDD_1") (pintype "input"))
      (node (ref "LED19") (pin "1") (pinfunction "VDD_1") (pintype "input"))
      (node (ref "LED2") (pin "1") (pinfunction "VDD_1") (pintype "input"))
      (node (ref "LED20") (pin "1") (pinfunction "VDD_1") (pintype "input"))
      (node (ref "LED21") (pin "1") (pinfunction "VDD_1") (pintype "input"))
      (node (ref "LED22") (pin "1") (pinfunction "VDD_1") (pintype "input"))
      (node (ref "LED23") (pin "1") (pinfunction "VDD_1") (pintype "input"))
      (node (ref "LED24") (pin "1") (pinfunction "VDD_1") (pintype "input"))
      (node (ref "LED25") (pin "1") (pinfunction "VDD_1") (pintype "input"))
      (node (ref "LED26") (pin "1") (pinfunction "VDD_1") (pintype "input"))
      (node (ref "LED27") (pin "1") (pinfunction "VDD_1") (pintype "input"))
      (node (ref "LED28") (pin "1") (pinfunction "VDD_1") (pintype "input"))
      (node (ref "LED29") (pin "1") (pinfunction "VDD_1") (pintype "input"))
      (node (ref "LED3") (pin "1") (pinfunction "VDD_1") (pintype "input"))
      (node (ref "LED30") (pin "1") (pinfunction "VDD_1") (pintype "input"))
      (node (ref "LED31") (pin "1") (pinfunction "VDD_1") (pintype "input"))
      (node (ref "LED32") (pin "1") (pinfunction "VDD_1") (pintype "input"))
      (node (ref "LED33") (pin "1") (pinfunction "VDD_1") (pintype "input"))
      (node (ref "LED34") (pin "1") (pinfunction "VDD_1") (pintype "input"))
      (node (ref "LED35") (pin "1") (pinfunction "VDD_1") (pintype "input"))
      (node (ref "LED36") (pin "1") (pinfunction "VDD_1") (pintype "input"))
      (node (ref "LED37") (pin "1") (pinfunction "VDD_1") (pintype "input"))
      (node (ref "LED38") (pin "1") (pinfunction "VDD_1") (pintype "input"))
      (node (ref "LED39") (pin "1") (pinfunction "VDD_1") (pintype "input"))
      (node (ref "LED4") (pin "1") (pinfunction "VDD_1") (pintype "input"))
      (node (ref "LED40") (pin "1") (pinfunction "VDD_1") (pintype "input"))
      (node (ref "LED41") (pin "1") (pinfunction "VDD_1") (pintype "input"))
      (node (ref "LED42") (pin "1") (pinfunction "VDD_1") (pintype "input"))
      (node (ref "LED43") (pin "1") (pinfunction "VDD_1") (pintype "input"))
      (node (ref "LED44") (pin "1") (pinfunction "VDD_1") (pintype "input"))
      (node (ref "LED45") (pin "1") (pinfunction "VDD_1") (pintype "input"))
      (node (ref "LED46") (pin "1") (pinfunction "VDD_1") (pintype "input"))
      (node (ref "LED47") (pin "1") (pinfunction "VDD_1") (pintype "input"))
      (node (ref "LED48") (pin "1") (pinfunction "VDD_1") (pintype "input"))
      (node (ref "LED49") (pin "1") (pinfunction "VDD_1") (pintype "input"))
      (node (ref "LED5") (pin "1") (pinfunction "VDD_1") (pintype "input"))
      (node (ref "LED50") (pin "1") (pinfunction "VDD_1") (pintype "input"))
      (node (ref "LED51") (pin "1") (pinfunction "VDD_1") (pintype "input"))
      (node (ref "LED52") (pin "1") (pinfunction "VDD_1") (pintype "input"))
      (node (ref "LED53") (pin "1") (pinfunction "VDD_1") (pintype "input"))
      (node (ref "LED54") (pin "1") (pinfunction "VDD_1") (pintype "input"))
      (node (ref "LED55") (pin "1") (pinfunction "VDD_1") (pintype "input"))
      (node (ref "LED56") (pin "1") (pinfunction "VDD_1") (pintype "input"))
      (node (ref "LED57") (pin "1") (pinfunction "VDD_1") (pintype "input"))
      (node (ref "LED58") (pin "1") (pinfunction "VDD_1") (pintype "input"))
      (node (ref "LED59") (pin "1") (pinfunction "VDD_1") (pintype "input"))
      (node (ref "LED6") (pin "1") (pinfunction "VDD_1") (pintype "input"))
      (node (ref "LED60") (pin "1") (pinfunction "VDD_1") (pintype "input"))
      (node (ref "LED61") (pin "1") (pinfunction "VDD_1") (pintype "input"))
      (node (ref "LED62") (pin "1") (pinfunction "VDD_1") (pintype "input"))
      (node (ref "LED63") (pin "1") (pinfunction "VDD_1") (pintype "input"))
      (node (ref "LED7") (pin "1") (pinfunction "VDD_1") (pintype "input"))
      (node (ref "LED8") (pin "1") (pinfunction "VDD_1") (pintype "input"))
      (node (ref "LED9") (pin "1") (pinfunction "VDD_1") (pintype "input"))
    )
    (net (code "4") (name "GND") (class "Default")
      (node (ref "C0") (pin "2") (pinfunction "2_2") (pintype "input"))
      (node (ref "C1") (pin "2") (pinfunction "2_2") (pintype "input"))
      (node (ref "C10") (pin "2") (pinfunction "2_2") (pintype "input"))
      (node (ref "C11") (pin "2") (pinfunction "2_2") (pintype "input"))
      (node (ref "C12") (pin "2") (pinfunction "2_2") (pintype "input"))
      (node (ref "C13") (pin "2") (pinfunction "2_2") (pintype "input"))
      (node (ref "C14") (pin "2") (pinfunction "2_2") (pintype "input"))
      (node (ref "C15") (pin "2") (pinfunction "2_2") (pintype "input"))
      (node (ref "C16") (pin "2") (pinfunction "2_2") (pintype "input"))
      (node (ref "C17") (pin "2") (pinfunction "2_2") (pintype "input"))
      (node (ref "C18") (pin "2") (pinfunction "2_2") (pintype "input"))
      (node (ref "C19") (pin "2") (pinfunction "2_2") (pintype "input"))
      (node (ref "C2") (pin "2") (pinfunction "2_2") (pintype "input"))
      (node (ref "C20") (pin "2") (pinfunction "2_2") (pintype "input"))
      (node (ref "C21") (pin "2") (pinfunction "2_2") (pintype "input"))
      (node (ref "C22") (pin "2") (pinfunction "2_2") (pintype "input"))
      (node (ref "C23") (pin "2") (pinfunction "2_2") (pintype "input"))
      (node (ref "C24") (pin "2") (pinfunction "2_2") (pintype "input"))
      (node (ref "C25") (pin "2") (pinfunction "2_2") (pintype "input"))
      (node (ref "C26") (pin "2") (pinfunction "2_2") (pintype "input"))
      (node (ref "C27") (pin "2") (pinfunction "2_2") (pintype "input"))
      (node (ref "C28") (pin "2") (pinfunction "2_2") (pintype "input"))
      (node (ref "C29") (pin "2") (pinfunction "2_2") (pintype "input"))
      (node (ref "C3") (pin "2") (pinfunction "2_2") (pintype "input"))
      (node (ref "C30") (pin "2") (pinfunction "2_2") (pintype "input"))
      (node (ref "C31") (pin "2") (pinfunction "2_2") (pintype "input"))
      (node (ref "C32") (pin "2") (pinfunction "2_2") (pintype "input"))
      (node (ref "C33") (pin "2") (pinfunction "2_2") (pintype "input"))
      (node (ref "C34") (pin "2") (pinfunction "2_2") (pintype "input"))
      (node (ref "C35") (pin "2") (pinfunction "2_2") (pintype "input"))
      (node (ref "C36") (pin "2") (pinfunction "2_2") (pintype "input"))
      (node (ref "C37") (pin "2") (pinfunction "2_2") (pintype "input"))
      (node (ref "C38") (pin "2") (pinfunction "2_2") (pintype "input"))
      (node (ref "C39") (pin "2") (pinfunction "2_2") (pintype "input"))
      (node (ref "C4") (pin "2") (pinfunction "2_2") (pintype "input"))
      (node (ref "C40") (pin "2") (pinfunction "2_2") (pintype "input"))
      (node (ref "C41") (pin "2") (pinfunction "2_2") (pintype "input"))
      (node (ref "C42") (pin "2") (pinfunction "2_2") (pintype "input"))
      (node (ref "C43") (pin "2") (pinfunction "2_2") (pintype "input"))
      (node (ref "C44") (pin "2") (pinfunction "2_2") (pintype "input"))
      (node (ref "C45") (pin "2") (pinfunction "2_2") (pintype "input"))
      (node (ref "C46") (pin "2") (pinfunction "2_2") (pintype "input"))
      (node (ref "C47") (pin "2") (pinfunction "2_2") (pintype "input"))
      (node (ref "C48") (pin "2") (pinfunction "2_2") (pintype "input"))
      (node (ref "C49") (pin "2") (pinfunction "2_2") (pintype "input"))
      (node (ref "C5") (pin "2") (pinfunction "2_2") (pintype "input"))
      (node (ref "C50") (pin "2") (pinfunction "2_2") (pintype "input"))
      (node (ref "C51") (pin "2") (pinfunction "2_2") (pintype "input"))
      (node (ref "C52") (pin "2") (pinfunction "2_2") (pintype "input"))
      (node (ref "C53") (pin "2") (pinfunction "2_2") (pintype "input"))
      (node (ref "C54") (pin "2") (pinfunction "2_2") (pintype "input"))
      (node (ref "C55") (pin "2") (pinfunction "2_2") (pintype "input"))
      (node (ref "C56") (pin "2") (pinfunction "2_2") (pintype "input"))
      (node (ref "C57") (pin "2") (pinfunction "2_2") (pintype "input"))
      (node (ref "C58") (pin "2") (pinfunction "2_2") (pintype "input"))
      (node (ref "C59") (pin "2") (pinfunction "2_2") (pintype "input"))
      (node (ref "C6") (pin "2") (pinfunction "2_2") (pintype "input"))
      (node (ref "C60") (pin "2") (pinfunction "2_2") (pintype "input"))
      (node (ref "C61") (pin "2") (pinfunction "2_2") (pintype "input"))
      (node (ref "C62") (pin "2") (pinfunction "2_2") (pintype "input"))
      (node (ref "C63") (pin "2") (pinfunction "2_2") (pintype "input"))
      (node (ref "C7") (pin "2") (pinfunction "2_2") (pintype "input"))
      (node (ref "C8") (pin "2") (pinfunction "2_2") (pintype "input"))
      (node (ref "C9") (pin "2") (pinfunction "2_2") (pintype "input"))
      (node (ref "H1") (pin "3") (pinfunction "3_3") (pintype "input"))
      (node (ref "H2") (pin "3") (pinfunction "3_3") (pintype "input"))
      (node (ref "LED0") (pin "3") (pinfunction "VSS_3") (pintype "input"))
      (node (ref "LED1") (pin "3") (pinfunction "VSS_3") (pintype "input"))
      (node (ref "LED10") (pin "3") (pinfunction "VSS_3") (pintype "input"))
      (node (ref "LED11") (pin "3") (pinfunction "VSS_3") (pintype "input"))
      (node (ref "LED12") (pin "3") (pinfunction "VSS_3") (pintype "input"))
      (node (ref "LED13") (pin "3") (pinfunction "VSS_3") (pintype "input"))
      (node (ref "LED14") (pin "3") (pinfunction "VSS_3") (pintype "input"))
      (node (ref "LED15") (pin "3") (pinfunction "VSS_3") (pintype "input"))
      (node (ref "LED16") (pin "3") (pinfunction "VSS_3") (pintype "input"))
      (node (ref "LED17") (pin "3") (pinfunction "VSS_3") (pintype "input"))
      (node (ref "LED18") (pin "3") (pinfunction "VSS_3") (pintype "input"))
      (node (ref "LED19") (pin "3") (pinfunction "VSS_3") (pintype "input"))
      (node (ref "LED2") (pin "3") (pinfunction "VSS_3") (pintype "input"))
      (node (ref "LED20") (pin "3") (pinfunction "VSS_3") (pintype "input"))
      (node (ref "LED21") (pin "3") (pinfunction "VSS_3") (pintype "input"))
      (node (ref "LED22") (pin "3") (pinfunction "VSS_3") (pintype "input"))
      (node (ref "LED23") (pin "3") (pinfunction "VSS_3") (pintype "input"))
      (node (ref "LED24") (pin "3") (pinfunction "VSS_3") (pintype "input"))
      (node (ref "LED25") (pin "3") (pinfunction "VSS_3") (pintype "input"))
      (node (ref "LED26") (pin "3") (pinfunction "VSS_3") (pintype "input"))
      (node (ref "LED27") (pin "3") (pinfunction "VSS_3") (pintype "input"))
      (node (ref "LED28") (pin "3") (pinfunction "VSS_3") (pintype "input"))
      (node (ref "LED29") (pin "3") (pinfunction "VSS_3") (pintype "input"))
      (node (ref "LED3") (pin "3") (pinfunction "VSS_3") (pintype "input"))
      (node (ref "LED30") (pin "3") (pinfunction "VSS_3") (pintype "input"))
      (node (ref "LED31") (pin "3") (pinfunction "VSS_3") (pintype "input"))
      (node (ref "LED32") (pin "3") (pinfunction "VSS_3") (pintype "input"))
      (node (ref "LED33") (pin "3") (pinfunction "VSS_3") (pintype "input"))
      (node (ref "LED34") (pin "3") (pinfunction "VSS_3") (pintype "input"))
      (node (ref "LED35") (pin "3") (pinfunction "VSS_3") (pintype "input"))
      (node (ref "LED36") (pin "3") (pinfunction "VSS_3") (pintype "input"))
      (node (ref "LED37") (pin "3") (pinfunction "VSS_3") (pintype "input"))
      (node (ref "LED38") (pin "3") (pinfunction "VSS_3") (pintype "input"))
      (node (ref "LED39") (pin "3") (pinfunction "VSS_3") (pintype "input"))
      (node (ref "LED4") (pin "3") (pinfunction "VSS_3") (pintype "input"))
      (node (ref "LED40") (pin "3") (pinfunction "VSS_3") (pintype "input"))
      (node (ref "LED41") (pin "3") (pinfunction "VSS_3") (pintype "input"))
      (node (ref "LED42") (pin "3") (pinfunction "VSS_3") (pintype "input"))
      (node (ref "LED43") (pin "3") (pinfunction "VSS_3") (pintype "input"))
      (node (ref "LED44") (pin "3") (pinfunction "VSS_3") (pintype "input"))
      (node (ref "LED45") (pin "3") (pinfunction "VSS_3") (pintype "input"))
      (node (ref "LED46") (pin "3") (pinfunction "VSS_3") (pintype "input"))
      (node (ref "LED47") (pin "3") (pinfunction "VSS_3") (pintype "input"))
      (node (ref "LED48") (pin "3") (pinfunction "VSS_3") (pintype "input"))
      (node (ref "LED49") (pin "3") (pinfunction "VSS_3") (pintype "input"))
      (node (ref "LED5") (pin "3") (pinfunction "VSS_3") (pintype "input"))
      (node (ref "LED50") (pin "3") (pinfunction "VSS_3") (pintype "input"))
      (node (ref "LED51") (pin "3") (pinfunction "VSS_3") (pintype "input"))
      (node (ref "LED52") (pin "3") (pinfunction "VSS_3") (pintype "input"))
      (node (ref "LED53") (pin "3") (pinfunction "VSS_3") (pintype "input"))
      (node (ref "LED54") (pin "3") (pinfunction "VSS_3") (pintype "input"))
      (node (ref "LED55") (pin "3") (pinfunction "VSS_3") (pintype "input"))
      (node (ref "LED56") (pin "3") (pinfunction "VSS_3") (pintype "input"))
      (node (ref "LED57") (pin "3") (pinfunction "VSS_3") (pintype "input"))
      (node (ref "LED58") (pin "3") (pinfunction "VSS_3") (pintype "input"))
      (node (ref "LED59") (pin "3") (pinfunction "VSS_3") (pintype "input"))
      (node (ref "LED6") (pin "3") (pinfunction "VSS_3") (pintype "input"))
      (node (ref "LED60") (pin "3") (pinfunction "VSS_3") (pintype "input"))
      (node (ref "LED61") (pin "3") (pinfunction "VSS_3") (pintype "input"))
      (node (ref "LED62") (pin "3") (pinfunction "VSS_3") (pintype "input"))
      (node (ref "LED63") (pin "3") (pinfunction "VSS_3") (pintype "input"))
      (node (ref "LED7") (pin "3") (pinfunction "VSS_3") (pintype "input"))
      (node (ref "LED8") (pin "3") (pinfunction "VSS_3") (pintype "input"))
      (node (ref "LED9") (pin "3") (pinfunction "VSS_3") (pintype "input"))
    )
    (net (code "5") (name "Net-(LED0-DOUT)") (class "Default")
      (node (ref "LED0") (pin "2") (pinfunction "DOUT_2") (pintype "input"))
      (node (ref "LED1") (pin "4") (pinfunction "DIN_4") (pintype "input"))
    )
    (net (code "6") (name "Net-(LED1-DOUT)") (class "Default")
      (node (ref "LED1") (pin "2") (pinfunction "DOUT_2") (pintype "input"))
      (node (ref "LED2") (pin "4") (pinfunction "DIN_4") (pintype "input"))
    )
    (net (code "7") (name "Net-(LED2-DOUT)") (class "Default")
      (node (ref "LED2") (pin "2") (pinfunction "DOUT_2") (pintype "input"))
      (node (ref "LED3") (pin "4") (pinfunction "DIN_4") (pintype "input"))
    )
    (net (code "8") (name "Net-(LED3-DOUT)") (class "Default")
      (node (ref "LED3") (pin "2") (pinfunction "DOUT_2") (pintype "input"))
      (node (ref "LED4") (pin "4") (pinfunction "DIN_4") (pintype "input"))
    )
    (net (code "9") (name "Net-(LED4-DOUT)") (class "Default")
      (node (ref "LED4") (pin "2") (pinfunction "DOUT_2") (pintype "input"))
      (node (ref "LED5") (pin "4") (pinfunction "DIN_4") (pintype "input"))
    )
    (net (code "10") (name "Net-(LED5-DOUT)") (class "Default")
      (node (ref "LED5") (pin "2") (pinfunction "DOUT_2") (pintype "input"))
      (node (ref "LED6") (pin "4") (pinfunction "DIN_4") (pintype "input"))
    )
    (net (code "11") (name "Net-(LED6-DOUT)") (class "Default")
      (node (ref "LED6") (pin "2") (pinfunction "DOUT_2") (pintype "input"))
      (node (ref "LED7") (pin "4") (pinfunction "DIN_4") (pintype "input"))
    )
    (net (code "12") (name "Net-(LED7-DOUT)") (class "Default")
      (node (ref "LED7") (pin "2") (pinfunction "DOUT_2") (pintype "input"))
      (node (ref "LED8") (pin "4") (pinfunction "DIN_4") (pintype "input"))
    )
    (net (code "13") (name "Net-(LED8-DOUT)") (class "Default")
      (node (ref "LED8") (pin "2") (pinfunction "DOUT_2") (pintype "input"))
      (node (ref "LED9") (pin "4") (pinfunction "DIN_4") (pintype "input"))
    )
    (net (code "14") (name "Net-(LED10-DIN)") (class "Default")
      (node (ref "LED10") (pin "4") (pinfunction "DIN_4") (pintype "input"))
      (node (ref "LED9") (pin "2") (pinfunction "DOUT_2") (pintype "input"))
    )
    (net (code "15") (name "Net-(LED10-DOUT)") (class "Default")
      (node (ref "LED10") (pin "2") (pinfunction "DOUT_2") (pintype "input"))
      (node (ref "LED11") (pin "4") (pinfunction "DIN_4") (pintype "input"))
    )
    (net (code "16") (name "Net-(LED11-DOUT)") (class "Default")
      (node (ref "LED11") (pin "2") (pinfunction "DOUT_2") (pintype "input"))
      (node (ref "LED12") (pin "4") (pinfunction "DIN_4") (pintype "input"))
    )
    (net (code "17") (name "Net-(LED12-DOUT)") (class "Default")
      (node (ref "LED12") (pin "2") (pinfunction "DOUT_2") (pintype "input"))
      (node (ref "LED13") (pin "4") (pinfunction "DIN_4") (pintype "input"))
    )
    (net (code "18") (name "Net-(LED13-DOUT)") (class "Default")
      (node (ref "LED13") (pin "2") (pinfunction "DOUT_2") (pintype "input"))
      (node (ref "LED14") (pin "4") (pinfunction "DIN_4") (pintype "input"))
    )
    (net (code "19") (name "Net-(LED14-DOUT)") (class "Default")
      (node (ref "LED14") (pin "2") (pinfunction "DOUT_2") (pintype "input"))
      (node (ref "LED15") (pin "4") (pinfunction "DIN_4") (pintype "input"))
    )
    (net (code "20") (name "Net-(LED15-DOUT)") (class "Default")
      (node (ref "LED15") (pin "2") (pinfunction "DOUT_2") (pintype "input"))
      (node (ref "LED16") (pin "4") (pinfunction "DIN_4") (pintype "input"))
    )
    (net (code "21") (name "Net-(LED16-DOUT)") (class "Default")
      (node (ref "LED16") (pin "2") (pinfunction "DOUT_2") (pintype "input"))
      (node (ref "LED17") (pin "4") (pinfunction "DIN_4") (pintype "input"))
    )
    (net (code "22") (name "Net-(LED17-DOUT)") (class "Default")
      (node (ref "LED17") (pin "2") (pinfunction "DOUT_2") (pintype "input"))
      (node (ref "LED18") (pin "4") (pinfunction "DIN_4") (pintype "input"))
    )
    (net (code "23") (name "Net-(LED18-DOUT)") (class "Default")
      (node (ref "LED18") (pin "2") (pinfunction "DOUT_2") (pintype "input"))
      (node (ref "LED19") (pin "4") (pinfunction "DIN_4") (pintype "input"))
    )
    (net (code "24") (name "Net-(LED19-DOUT)") (class "Default")
      (node (ref "LED19") (pin "2") (pinfunction "DOUT_2") (pintype "input"))
      (node (ref "LED20") (pin "4") (pinfunction "DIN_4") (pintype "input"))
    )
    (net (code "25") (name "Net-(LED20-DOUT)") (class "Default")
      (node (ref "LED20") (pin "2") (pinfunction "DOUT_2") (pintype "input"))
      (node (ref "LED21") (pin "4") (pinfunction "DIN_4") (pintype "input"))
    )
    (net (code "26") (name "Net-(LED21-DOUT)") (class "Default")
      (node (ref "LED21") (pin "2") (pinfunction "DOUT_2") (pintype "input"))
      (node (ref "LED22") (pin "4") (pinfunction "DIN_4") (pintype "input"))
    )
    (net (code "27") (name "Net-(LED22-DOUT)") (class "Default")
      (node (ref "LED22") (pin "2") (pinfunction "DOUT_2") (pintype "input"))
      (node (ref "LED23") (pin "4") (pinfunction "DIN_4") (pintype "input"))
    )
    (net (code "28") (name "Net-(LED23-DOUT)") (class "Default")
      (node (ref "LED23") (pin "2") (pinfunction "DOUT_2") (pintype "input"))
      (node (ref "LED24") (pin "4") (pinfunction "DIN_4") (pintype "input"))
    )
    (net (code "29") (name "Net-(LED24-DOUT)") (class "Default")
      (node (ref "LED24") (pin "2") (pinfunction "DOUT_2") (pintype "input"))
      (node (ref "LED25") (pin "4") (pinfunction "DIN_4") (pintype "input"))
    )
    (net (code "30") (name "Net-(LED25-DOUT)") (class "Default")
      (node (ref "LED25") (pin "2") (pinfunction "DOUT_2") (pintype "input"))
      (node (ref "LED26") (pin "4") (pinfunction "DIN_4") (pintype "input"))
    )
    (net (code "31") (name "Net-(LED26-DOUT)") (class "Default")
      (node (ref "LED26") (pin "2") (pinfunction "DOUT_2") (pintype "input"))
      (node (ref "LED27") (pin "4") (pinfunction "DIN_4") (pintype "input"))
    )
    (net (code "32") (name "Net-(LED27-DOUT)") (class "Default")
      (node (ref "LED27") (pin "2") (pinfunction "DOUT_2") (pintype "input"))
      (node (ref "LED28") (pin "4") (pinfunction "DIN_4") (pintype "input"))
    )
    (net (code "33") (name "Net-(LED28-DOUT)") (class "Default")
      (node (ref "LED28") (pin "2") (pinfunction "DOUT_2") (pintype "input"))
      (node (ref "LED29") (pin "4") (pinfunction "DIN_4") (pintype "input"))
    )
    (net (code "34") (name "Net-(LED29-DOUT)") (class "Default")
      (node (ref "LED29") (pin "2") (pinfunction "DOUT_2") (pintype "input"))
      (node (ref "LED30") (pin "4") (pinfunction "DIN_4") (pintype "input"))
    )
    (net (code "35") (name "Net-(LED30-DOUT)") (class "Default")
      (node (ref "LED30") (pin "2") (pinfunction "DOUT_2") (pintype "input"))
      (node (ref "LED31") (pin "4") (pinfunction "DIN_4") (pintype "input"))
    )
    (net (code "36") (name "Net-(LED31-DOUT)") (class "Default")
      (node (ref "LED31") (pin "2") (pinfunction "DOUT_2") (pintype "input"))
      (node (ref "LED32") (pin "4") (pinfunction "DIN_4") (pintype "input"))
    )
    (net (code "37") (name "Net-(LED32-DOUT)") (class "Default")
      (node (ref "LED32") (pin "2") (pinfunction "DOUT_2") (pintype "input"))
      (node (ref "LED33") (pin "4") (pinfunction "DIN_4") (pintype "input"))
    )
    (net (code "38") (name "Net-(LED33-DOUT)") (class "Default")
      (node (ref "LED33") (pin "2") (pinfunction "DOUT_2") (pintype "input"))
      (node (ref "LED34") (pin "4") (pinfunction "DIN_4") (pintype "input"))
    )
    (net (code "39") (name "Net-(LED34-DOUT)") (class "Default")
      (node (ref "LED34") (pin "2") (pinfunction "DOUT_2") (pintype "input"))
      (node (ref "LED35") (pin "4") (pinfunction "DIN_4") (pintype "input"))
    )
    (net (code "40") (name "Net-(LED35-DOUT)") (class "Default")
      (node (ref "LED35") (pin "2") (pinfunction "DOUT_2") (pintype "input"))
      (node (ref "LED36") (pin "4") (pinfunction "DIN_4") (pintype "input"))
    )
    (net (code "41") (name "Net-(LED36-DOUT)") (class "Default")
      (node (ref "LED36") (pin "2") (pinfunction "DOUT_2") (pintype "input"))
      (node (ref "LED37") (pin "4") (pinfunction "DIN_4") (pintype "input"))
    )
    (net (code "42") (name "Net-(LED37-DOUT)") (class "Default")
      (node (ref "LED37") (pin "2") (pinfunction "DOUT_2") (pintype "input"))
      (node (ref "LED38") (pin "4") (pinfunction "DIN_4") (pintype "input"))
    )
    (net (code "43") (name "Net-(LED38-DOUT)") (class "Default")
      (node (ref "LED38") (pin "2") (pinfunction "DOUT_2") (pintype "input"))
      (node (ref "LED39") (pin "4") (pinfunction "DIN_4") (pintype "input"))
    )
    (net (code "44") (name "Net-(LED39-DOUT)") (class "Default")
      (node (ref "LED39") (pin "2") (pinfunction "DOUT_2") (pintype "input"))
      (node (ref "LED40") (pin "4") (pinfunction "DIN_4") (pintype "input"))
    )
    (net (code "45") (name "Net-(LED40-DOUT)") (class "Default")
      (node (ref "LED40") (pin "2") (pinfunction "DOUT_2") (pintype "input"))
      (node (ref "LED41") (pin "4") (pinfunction "DIN_4") (pintype "input"))
    )
    (net (code "46") (name "Net-(LED41-DOUT)") (class "Default")
      (node (ref "LED41") (pin "2") (pinfunction "DOUT_2") (pintype "input"))
      (node (ref "LED42") (pin "4") (pinfunction "DIN_4") (pintype "input"))
    )
    (net (code "47") (name "Net-(LED42-DOUT)") (class "Default")
      (node (ref "LED42") (pin "2") (pinfunction "DOUT_2") (pintype "input"))
      (node (ref "LED43") (pin "4") (pinfunction "DIN_4") (pintype "input"))
    )
    (net (code "48") (name "Net-(LED43-DOUT)") (class "Default")
      (node (ref "LED43") (pin "2") (pinfunction "DOUT_2") (pintype "input"))
      (node (ref "LED44") (pin "4") (pinfunction "DIN_4") (pintype "input"))
    )
    (net (code "49") (name "Net-(LED44-DOUT)") (class "Default")
      (node (ref "LED44") (pin "2") (pinfunction "DOUT_2") (pintype "input"))
      (node (ref "LED45") (pin "4") (pinfunction "DIN_4") (pintype "input"))
    )
    (net (code "50") (name "Net-(LED45-DOUT)") (class "Default")
      (node (ref "LED45") (pin "2") (pinfunction "DOUT_2") (pintype "input"))
      (node (ref "LED46") (pin "4") (pinfunction "DIN_4") (pintype "input"))
    )
    (net (code "51") (name "Net-(LED46-DOUT)") (class "Default")
      (node (ref "LED46") (pin "2") (pinfunction "DOUT_2") (pintype "input"))
      (node (ref "LED47") (pin "4") (pinfunction "DIN_4") (pintype "input"))
    )
    (net (code "52") (name "Net-(LED47-DOUT)") (class "Default")
      (node (ref "LED47") (pin "2") (pinfunction "DOUT_2") (pintype "input"))
      (node (ref "LED48") (pin "4") (pinfunction "DIN_4") (pintype "input"))
    )
    (net (code "53") (name "Net-(LED48-DOUT)") (class "Default")
      (node (ref "LED48") (pin "2") (pinfunction "DOUT_2") (pintype "input"))
      (node (ref "LED49") (pin "4") (pinfunction "DIN_4") (pintype "input"))
    )
    (net (code "54") (name "Net-(LED49-DOUT)") (class "Default")
      (node (ref "LED49") (pin "2") (pinfunction "DOUT_2") (pintype "input"))
      (node (ref "LED50") (pin "4") (pinfunction "DIN_4") (pintype "input"))
    )
    (net (code "55") (name "Net-(LED50-DOUT)") (class "Default")
      (node (ref "LED50") (pin "2") (pinfunction "DOUT_2") (pintype "input"))
      (node (ref "LED51") (pin "4") (pinfunction "DIN_4") (pintype "input"))
    )
    (net (code "56") (name "Net-(LED51-DOUT)") (class "Default")
      (node (ref "LED51") (pin "2") (pinfunction "DOUT_2") (pintype "input"))
      (node (ref "LED52") (pin "4") (pinfunction "DIN_4") (pintype "input"))
    )
    (net (code "57") (name "Net-(LED52-DOUT)") (class "Default")
      (node (ref "LED52") (pin "2") (pinfunction "DOUT_2") (pintype "input"))
      (node (ref "LED53") (pin "4") (pinfunction "DIN_4") (pintype "input"))
    )
    (net (code "58") (name "Net-(LED53-DOUT)") (class "Default")
      (node (ref "LED53") (pin "2") (pinfunction "DOUT_2") (pintype "input"))
      (node (ref "LED54") (pin "4") (pinfunction "DIN_4") (pintype "input"))
    )
    (net (code "59") (name "Net-(LED54-DOUT)") (class "Default")
      (node (ref "LED54") (pin "2") (pinfunction "DOUT_2") (pintype "input"))
      (node (ref "LED55") (pin "4") (pinfunction "DIN_4") (pintype "input"))
    )
    (net (code "60") (name "Net-(LED55-DOUT)") (class "Default")
      (node (ref "LED55") (pin "2") (pinfunction "DOUT_2") (pintype "input"))
      (node (ref "LED56") (pin "4") (pinfunction "DIN_4") (pintype "input"))
    )
    (net (code "61") (name "Net-(LED56-DOUT)") (class "Default")
      (node (ref "LED56") (pin "2") (pinfunction "DOUT_2") (pintype "input"))
      (node (ref "LED57") (pin "4") (pinfunction "DIN_4") (pintype "input"))
    )
    (net (code "62") (name "Net-(LED57-DOUT)") (class "Default")
      (node (ref "LED57") (pin "2") (pinfunction "DOUT_2") (pintype "input"))
      (node (ref "LED58") (pin "4") (pinfunction "DIN_4") (pintype "input"))
    )
    (net (code "63") (name "Net-(LED58-DOUT)") (class "Default")
      (node (ref "LED58") (pin "2") (pinfunction "DOUT_2") (pintype "input"))
      (node (ref "LED59") (pin "4") (pinfunction "DIN_4") (pintype "input"))
    )
    (net (code "64") (name "Net-(LED59-DOUT)") (class "Default")
      (node (ref "LED59") (pin "2") (pinfunction "DOUT_2") (pintype "input"))
      (node (ref "LED60") (pin "4") (pinfunction "DIN_4") (pintype "input"))
    )
    (net (code "65") (name "Net-(LED60-DOUT)") (class "Default")
      (node (ref "LED60") (pin "2") (pinfunction "DOUT_2") (pintype "input"))
      (node (ref "LED61") (pin "4") (pinfunction "DIN_4") (pintype "input"))
    )
    (net (code "66") (name "Net-(LED61-DOUT)") (class "Default")
      (node (ref "LED61") (pin "2") (pinfunction "DOUT_2") (pintype "input"))
      (node (ref "LED62") (pin "4") (pinfunction "DIN_4") (pintype "input"))
    )
    (net (code "67") (name "Net-(LED62-DOUT)") (class "Default")
      (node (ref "LED62") (pin "2") (pinfunction "DOUT_2") (pintype "input"))
      (node (ref "LED63") (pin "4") (pinfunction "DIN_4") (pintype "input"))
    )
  )
)
